# ESP32-Skunk1-OSHPARK.net
KiCad netlist of a schematic drawn in EAGLE
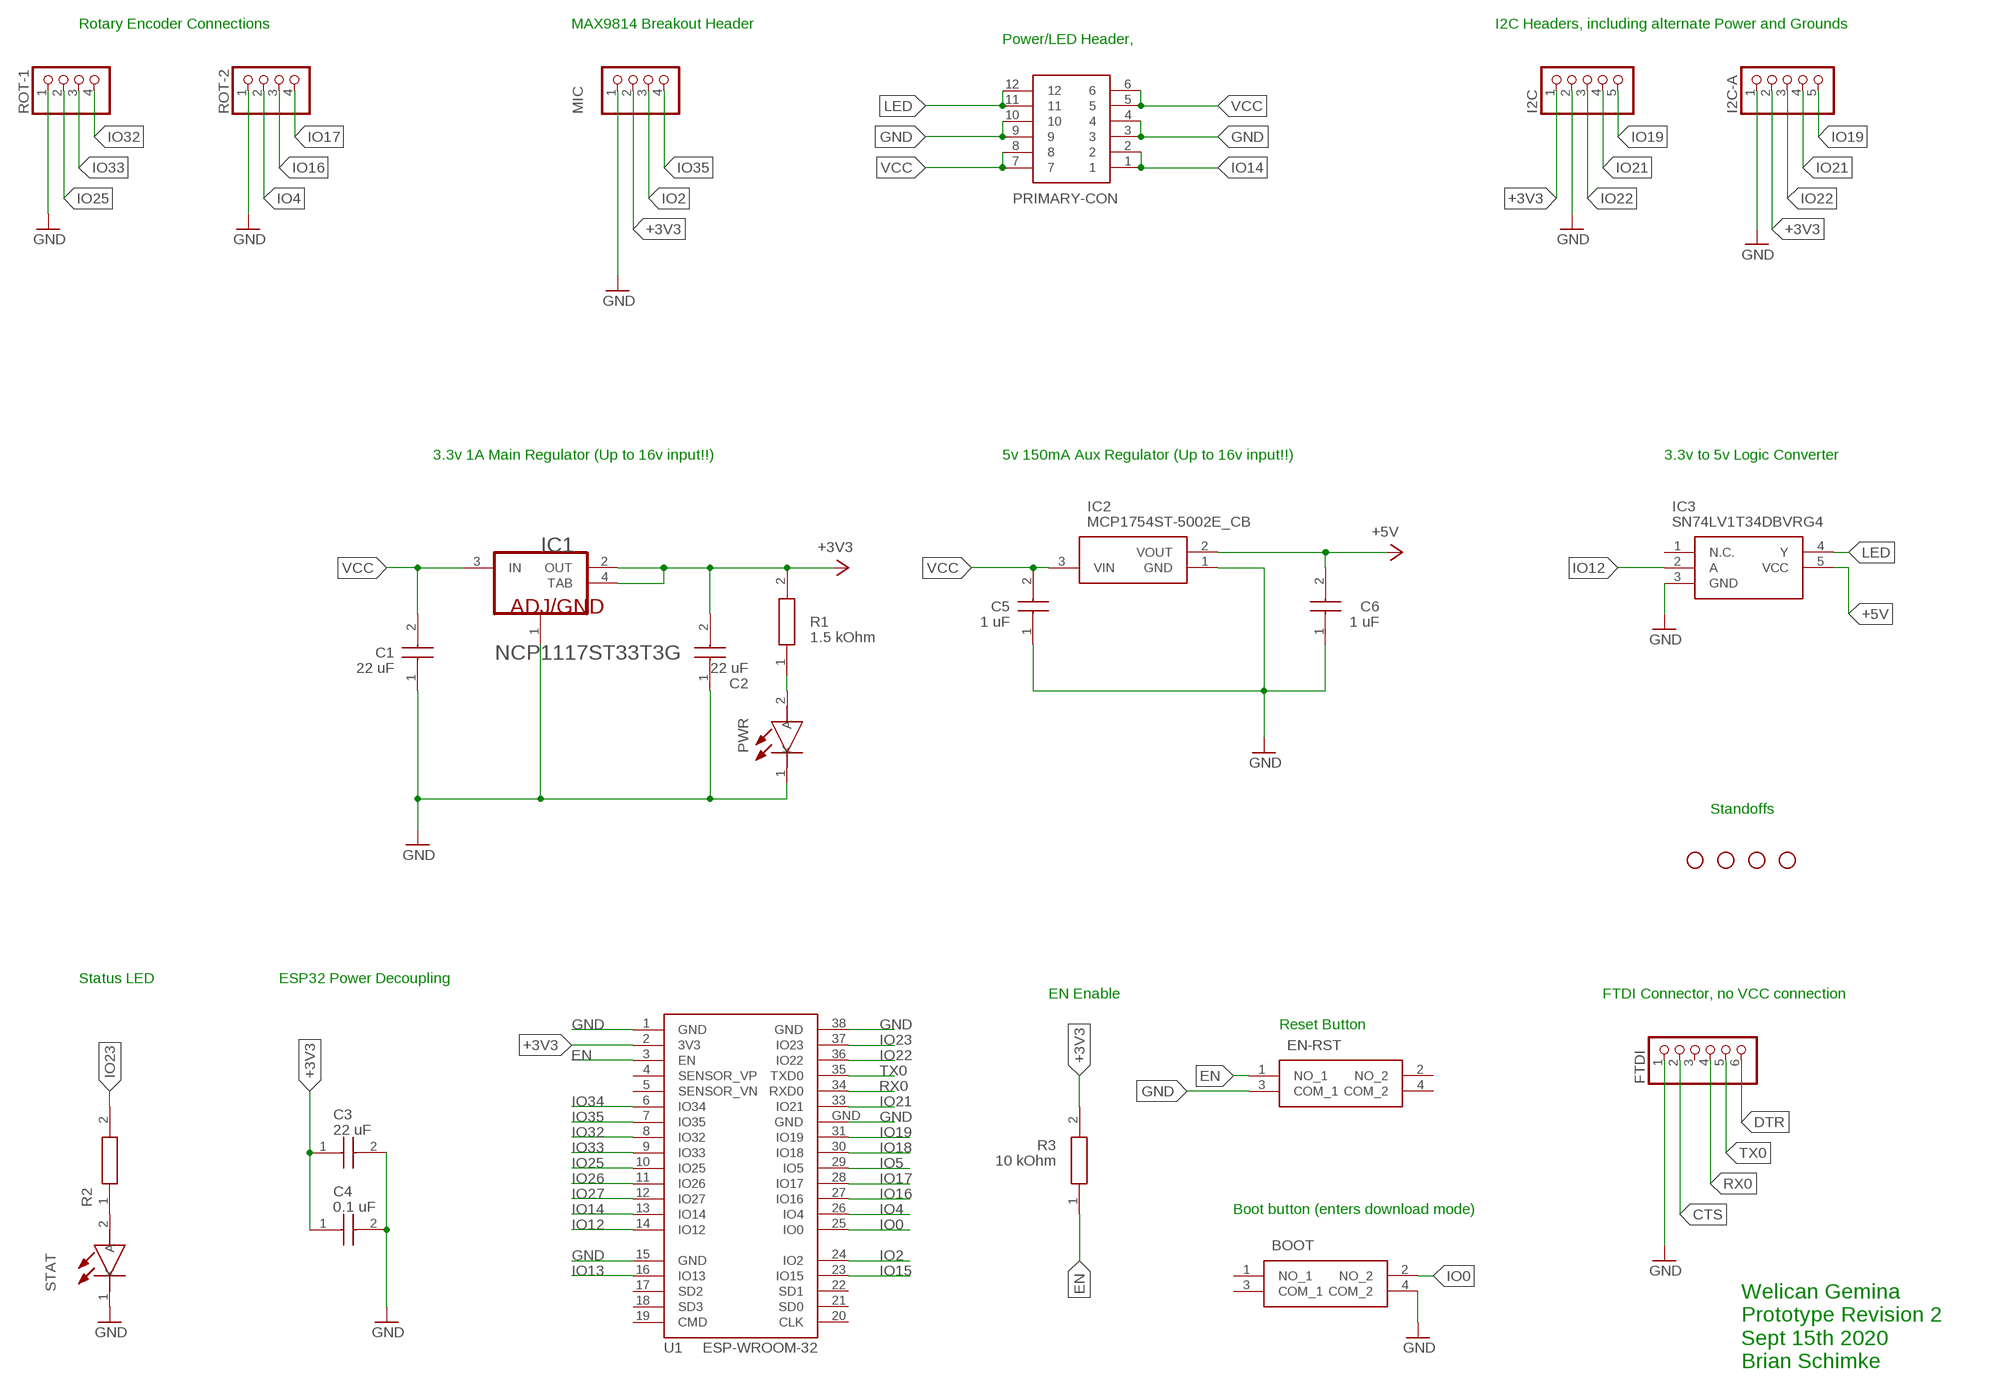
[diagram p0: schematic, sheet 1]

(export (version "E")
  (design (tool "Eeschema 10.0.6"))
  (components
    (comp (ref "BOOT")
      (value "PTS647SK70SMTR2LFS")
      (footprint "eagle-import:PTS647SK70SMTR2LFS")
      (fields (field (name "MOUSER_PART_NUMBER") "611-PTS647SK70SMTR2L"))
      (libsource (lib "eagle-import") (part "PTS647SK70SMTR2LFS"))
    )
    (comp (ref "C1")
      (value "22 uF")
      (footprint "eagle-import:CAPC3216X180N")
      (fields
        (field (name "MANUFACTURER_PART_NUMBER") "C1206C226M4PACTU")
        (field (name "MOUSER_PART_NUMBER") "80-C1206C226M4P")
      )
      (libsource (lib "eagle-import") (part "C1206C226M4PACTU"))
    )
    (comp (ref "C2")
      (value "22 uF")
      (footprint "eagle-import:CAPC3216X180N")
      (fields
        (field (name "MANUFACTURER_PART_NUMBER") "C1206C226M4PACTU")
        (field (name "MOUSER_PART_NUMBER") "80-C1206C226M4P")
      )
      (libsource (lib "eagle-import") (part "C1206C226M4PACTU"))
    )
    (comp (ref "C3")
      (value "22 uF")
      (footprint "eagle-import:CAPC3216X180N")
      (fields
        (field (name "MANUFACTURER_PART_NUMBER") "C1206C226M4PACTU")
        (field (name "MOUSER_PART_NUMBER") "80-C1206C226M4P")
      )
      (libsource (lib "eagle-import") (part "C1206C226M4PACTU"))
    )
    (comp (ref "C4")
      (value "0.1 uF")
      (footprint "eagle-import:CAPC3216X180N")
      (fields
        (field (name "MANUFACTURER_PART_NUMBER") "C1206C226M4PACTU")
        (field (name "MOUSER_PART_NUMBER") "80-C1206C226M4P")
      )
      (libsource (lib "eagle-import") (part "C1206C226M4PACTU"))
    )
    (comp (ref "C5")
      (value "1 uF")
      (footprint "eagle-import:CAPC3216X180N")
      (fields
        (field (name "MANUFACTURER_PART_NUMBER") "C1206C226M4PACTU")
        (field (name "MOUSER_PART_NUMBER") "80-C1206C226M4P")
      )
      (libsource (lib "eagle-import") (part "C1206C226M4PACTU"))
    )
    (comp (ref "C6")
      (value "1 uF")
      (footprint "eagle-import:CAPC3216X180N")
      (fields
        (field (name "MANUFACTURER_PART_NUMBER") "C1206C226M4PACTU")
        (field (name "MOUSER_PART_NUMBER") "80-C1206C226M4P")
      )
      (libsource (lib "eagle-import") (part "C1206C226M4PACTU"))
    )
    (comp (ref "EN-RST")
      (value "PTS647SK70SMTR2LFS")
      (footprint "eagle-import:PTS647SK70SMTR2LFS")
      (fields (field (name "MOUSER_PART_NUMBER") "611-PTS647SK70SMTR2L"))
      (libsource (lib "eagle-import") (part "PTS647SK70SMTR2LFS"))
    )
    (comp (ref "FTDI")
      (value "PINHD-1X6")
      (footprint "eagle-import:1X06")
      (libsource (lib "eagle-import") (part "PINHD-1X6"))
    )
    (comp (ref "H1")
      (value "STAND-OFF")
      (footprint "eagle-import:STAND-OFF")
      (libsource (lib "eagle-import") (part "STAND-OFF"))
    )
    (comp (ref "H2")
      (value "STAND-OFF")
      (footprint "eagle-import:STAND-OFF")
      (libsource (lib "eagle-import") (part "STAND-OFF"))
    )
    (comp (ref "H3")
      (value "STAND-OFF")
      (footprint "eagle-import:STAND-OFF")
      (libsource (lib "eagle-import") (part "STAND-OFF"))
    )
    (comp (ref "H4")
      (value "STAND-OFF")
      (footprint "eagle-import:STAND-OFF")
      (libsource (lib "eagle-import") (part "STAND-OFF"))
    )
    (comp (ref "I2C")
      (value "PINHD-1X5")
      (footprint "eagle-import:1X05")
      (libsource (lib "eagle-import") (part "PINHD-1X5"))
    )
    (comp (ref "I2C-A")
      (value "PINHD-1X5")
      (footprint "eagle-import:1X05")
      (libsource (lib "eagle-import") (part "PINHD-1X5"))
    )
    (comp (ref "IC1")
      (value "ON_SEMICONDUCTOR_NCP1117ST33T3GON_SEMICONDUCTOR_NCP1117ST33T3G_0_0")
      (footprint "eagle-import:ON_SEMICONDUCTOR_NCP1117ST33T3G_0")
      (fields
        (field (name "MF") "ON Semiconductor")
        (field (name "MPN") "NCP1117ST33T3G")
        (field (name "TOLERANCE") "1%")
      )
      (libsource (lib "eagle-import") (part "ON_SEMICONDUCTOR_NCP1117ST33T3GON_SEMICONDUCTOR_NCP1117ST33T3G_0_0"))
    )
    (comp (ref "IC2")
      (value "MCP1754ST-5002E_CB")
      (footprint "eagle-import:SOT95P255X145-3N")
      (fields
        (field (name "MANUFACTURER_PART_NUMBER") "MCP1754ST-5002E/CB")
        (field (name "MOUSER_PART_NUMBER") "579-MCP1754T-5002ECB")
      )
      (libsource (lib "eagle-import") (part "MCP1754ST-5002E_CB"))
    )
    (comp (ref "IC3")
      (value "SN74LV1T34DBVRG4")
      (footprint "eagle-import:SOT95P280X145-5N")
      (fields (field (name "MOUSER_PART_NUMBER") "595-SN74LV1T34DBVRG4"))
      (libsource (lib "eagle-import") (part "SN74LV1T34DBVRG4"))
    )
    (comp (ref "MIC")
      (value "PINHD-1X4")
      (footprint "eagle-import:1X04")
      (libsource (lib "eagle-import") (part "PINHD-1X4"))
    )
    (comp (ref "PRIMARY-CON")
      (value "1-2834015-6")
      (footprint "eagle-import:SHDR12W90P508X254_2X6_1824X128")
      (fields (field (name "MOUSER_PART_NUMBER") "571-1-2834015-6"))
      (libsource (lib "eagle-import") (part "1-2834015-6"))
    )
    (comp (ref "PWR")
      (value "150120AS75000")
      (footprint "eagle-import:LEDSC320X160X78-2N")
      (fields (field (name "MOUSER_PART_NUMBER") "710-150120AS75000"))
      (libsource (lib "eagle-import") (part "150120AS75000"))
    )
    (comp (ref "R1")
      (value "1.5 kOhm")
      (footprint "eagle-import:RESC3216X60N")
      (fields
        (field (name "MANUFACTURER_PART_NUMBER") "CRCW12061K00FKEB")
        (field (name "MOUSER_PART_NUMBER") "71-CRCW12061K00FKEB")
      )
      (libsource (lib "eagle-import") (part "CRCW12061K00FKEB"))
    )
    (comp (ref "R2")
      (value "CRCW12061K00FKEB")
      (footprint "eagle-import:RESC3216X60N")
      (fields (field (name "MOUSER_PART_NUMBER") "71-CRCW12061K00FKEB"))
      (libsource (lib "eagle-import") (part "CRCW12061K00FKEB"))
    )
    (comp (ref "R3")
      (value "10 kOhm")
      (footprint "eagle-import:RESC3216X60N")
      (fields
        (field (name "MANUFACTURER_PART_NUMBER") "CRCW12061K00FKEB")
        (field (name "MOUSER_PART_NUMBER") "71-CRCW12061K00FKEB")
      )
      (libsource (lib "eagle-import") (part "CRCW12061K00FKEB"))
    )
    (comp (ref "ROT-1")
      (value "PINHD-1X4")
      (footprint "eagle-import:1X04")
      (libsource (lib "eagle-import") (part "PINHD-1X4"))
    )
    (comp (ref "ROT-2")
      (value "PINHD-1X4")
      (footprint "eagle-import:1X04")
      (libsource (lib "eagle-import") (part "PINHD-1X4"))
    )
    (comp (ref "STAT")
      (value "150120AS75000")
      (footprint "eagle-import:LEDSC320X160X78-2N")
      (fields (field (name "MOUSER_PART_NUMBER") "710-150120AS75000"))
      (libsource (lib "eagle-import") (part "150120AS75000"))
    )
    (comp (ref "U1")
      (value "ESP-WROOM-32")
      (footprint "eagle-import:ESP-WROOM-32")
      (libsource (lib "eagle-import") (part "ESP-WROOM-32"))
    )
  )
  (nets
    (net (code "1") (name "+3V3") (class "Default")
      (node (ref "C2") (pin "2") (pinfunction "2_2") (pintype "bidirectional"))
      (node (ref "C3") (pin "1") (pinfunction "1_1") (pintype "bidirectional"))
      (node (ref "C4") (pin "1") (pinfunction "1_1") (pintype "bidirectional"))
      (node (ref "I2C") (pin "1") (pinfunction "1_1") (pintype "passive"))
      (node (ref "I2C-A") (pin "2") (pinfunction "2_2") (pintype "passive"))
      (node (ref "IC1") (pin "2") (pinfunction "OUT_2") (pintype "power_in"))
      (node (ref "IC1") (pin "4") (pinfunction "TAB_4") (pintype "passive"))
      (node (ref "MIC") (pin "2") (pinfunction "2_2") (pintype "passive"))
      (node (ref "R1") (pin "2") (pinfunction "2_2") (pintype "bidirectional"))
      (node (ref "R3") (pin "2") (pinfunction "2_2") (pintype "bidirectional"))
      (node (ref "U1") (pin "2") (pinfunction "3V3_2") (pintype "power_in"))
    )
    (net (code "2") (name "+5V") (class "Default")
      (node (ref "C6") (pin "2") (pinfunction "2_2") (pintype "bidirectional"))
      (node (ref "IC2") (pin "2") (pinfunction "VOUT_2") (pintype "bidirectional"))
      (node (ref "IC3") (pin "5") (pinfunction "VCC_5") (pintype "bidirectional"))
    )
    (net (code "3") (name "/IO5") (class "Default")
      (node (ref "U1") (pin "29") (pinfunction "IO5_29") (pintype "bidirectional"))
    )
    (net (code "4") (name "/IO13") (class "Default")
      (node (ref "U1") (pin "16") (pinfunction "IO13_16") (pintype "bidirectional"))
    )
    (net (code "5") (name "/IO15") (class "Default")
      (node (ref "U1") (pin "23") (pinfunction "IO15_23") (pintype "bidirectional"))
    )
    (net (code "6") (name "/IO18") (class "Default")
      (node (ref "U1") (pin "30") (pinfunction "IO18_30") (pintype "bidirectional"))
    )
    (net (code "7") (name "/IO26") (class "Default")
      (node (ref "U1") (pin "11") (pinfunction "IO26_11") (pintype "bidirectional"))
    )
    (net (code "8") (name "/IO27") (class "Default")
      (node (ref "U1") (pin "12") (pinfunction "IO27_12") (pintype "bidirectional"))
    )
    (net (code "9") (name "/IO34") (class "Default")
      (node (ref "U1") (pin "6") (pinfunction "IO34_6") (pintype "bidirectional"))
    )
    (net (code "10") (name "CTS") (class "Default")
      (node (ref "FTDI") (pin "2") (pinfunction "2_2") (pintype "passive"))
    )
    (net (code "11") (name "DTR") (class "Default")
      (node (ref "FTDI") (pin "6") (pinfunction "6_6") (pintype "passive"))
    )
    (net (code "12") (name "EN") (class "Default")
      (node (ref "EN-RST") (pin "1") (pinfunction "NO_1_1") (pintype "bidirectional"))
      (node (ref "R3") (pin "1") (pinfunction "1_1") (pintype "bidirectional"))
      (node (ref "U1") (pin "3") (pinfunction "EN_3") (pintype "input"))
    )
    (net (code "13") (name "GND") (class "Default")
      (node (ref "BOOT") (pin "4") (pinfunction "COM_2_4") (pintype "bidirectional"))
      (node (ref "C1") (pin "1") (pinfunction "1_1") (pintype "bidirectional"))
      (node (ref "C2") (pin "1") (pinfunction "1_1") (pintype "bidirectional"))
      (node (ref "C3") (pin "2") (pinfunction "2_2") (pintype "bidirectional"))
      (node (ref "C4") (pin "2") (pinfunction "2_2") (pintype "bidirectional"))
      (node (ref "C5") (pin "1") (pinfunction "1_1") (pintype "bidirectional"))
      (node (ref "C6") (pin "1") (pinfunction "1_1") (pintype "bidirectional"))
      (node (ref "EN-RST") (pin "3") (pinfunction "COM_1_3") (pintype "bidirectional"))
      (node (ref "FTDI") (pin "1") (pinfunction "1_1") (pintype "passive"))
      (node (ref "I2C") (pin "2") (pinfunction "2_2") (pintype "passive"))
      (node (ref "I2C-A") (pin "1") (pinfunction "1_1") (pintype "passive"))
      (node (ref "IC1") (pin "1") (pinfunction "ADJ/GND_1") (pintype "passive"))
      (node (ref "IC2") (pin "1") (pinfunction "GND_1") (pintype "bidirectional"))
      (node (ref "IC3") (pin "3") (pinfunction "GND_3") (pintype "bidirectional"))
      (node (ref "MIC") (pin "1") (pinfunction "1_1") (pintype "passive"))
      (node (ref "PRIMARY-CON") (pin "10") (pinfunction "10_10") (pintype "bidirectional"))
      (node (ref "PRIMARY-CON") (pin "3") (pinfunction "3_3") (pintype "bidirectional"))
      (node (ref "PRIMARY-CON") (pin "4") (pinfunction "4_4") (pintype "bidirectional"))
      (node (ref "PRIMARY-CON") (pin "9") (pinfunction "9_9") (pintype "bidirectional"))
      (node (ref "PWR") (pin "1") (pinfunction "K_1") (pintype "bidirectional"))
      (node (ref "ROT-1") (pin "1") (pinfunction "1_1") (pintype "passive"))
      (node (ref "ROT-2") (pin "1") (pinfunction "1_1") (pintype "passive"))
      (node (ref "STAT") (pin "1") (pinfunction "K_1") (pintype "bidirectional"))
      (node (ref "U1") (pin "1") (pinfunction "GND_1") (pintype "power_in"))
      (node (ref "U1") (pin "15") (pinfunction "GND_15") (pintype "power_in"))
      (node (ref "U1") (pin "38") (pinfunction "GND_38") (pintype "power_in"))
      (node (ref "U1") (pin "GND") (pinfunction "GND_GND") (pintype "power_in"))
    )
    (net (code "14") (name "IO0") (class "Default")
      (node (ref "BOOT") (pin "2") (pinfunction "NO_2_2") (pintype "bidirectional"))
      (node (ref "U1") (pin "25") (pinfunction "IO0_25") (pintype "bidirectional"))
    )
    (net (code "15") (name "IO2") (class "Default")
      (node (ref "MIC") (pin "3") (pinfunction "3_3") (pintype "passive"))
      (node (ref "U1") (pin "24") (pinfunction "IO2_24") (pintype "bidirectional"))
    )
    (net (code "16") (name "IO4") (class "Default")
      (node (ref "ROT-2") (pin "2") (pinfunction "2_2") (pintype "passive"))
      (node (ref "U1") (pin "26") (pinfunction "IO4_26") (pintype "bidirectional"))
    )
    (net (code "17") (name "IO12") (class "Default")
      (node (ref "IC3") (pin "2") (pinfunction "A_2") (pintype "bidirectional"))
      (node (ref "U1") (pin "14") (pinfunction "IO12_14") (pintype "bidirectional"))
    )
    (net (code "18") (name "IO14") (class "Default")
      (node (ref "PRIMARY-CON") (pin "1") (pinfunction "1_1") (pintype "bidirectional"))
      (node (ref "PRIMARY-CON") (pin "2") (pinfunction "2_2") (pintype "bidirectional"))
      (node (ref "U1") (pin "13") (pinfunction "IO14_13") (pintype "bidirectional"))
    )
    (net (code "19") (name "IO16") (class "Default")
      (node (ref "ROT-2") (pin "3") (pinfunction "3_3") (pintype "passive"))
      (node (ref "U1") (pin "27") (pinfunction "IO16_27") (pintype "bidirectional"))
    )
    (net (code "20") (name "IO17") (class "Default")
      (node (ref "ROT-2") (pin "4") (pinfunction "4_4") (pintype "passive"))
      (node (ref "U1") (pin "28") (pinfunction "IO17_28") (pintype "bidirectional"))
    )
    (net (code "21") (name "IO19") (class "Default")
      (node (ref "I2C") (pin "5") (pinfunction "5_5") (pintype "passive"))
      (node (ref "I2C-A") (pin "5") (pinfunction "5_5") (pintype "passive"))
      (node (ref "U1") (pin "31") (pinfunction "IO19_31") (pintype "bidirectional"))
    )
    (net (code "22") (name "IO21") (class "Default")
      (node (ref "I2C") (pin "4") (pinfunction "4_4") (pintype "passive"))
      (node (ref "I2C-A") (pin "4") (pinfunction "4_4") (pintype "passive"))
      (node (ref "U1") (pin "33") (pinfunction "IO21_33") (pintype "bidirectional"))
    )
    (net (code "23") (name "IO22") (class "Default")
      (node (ref "I2C") (pin "3") (pinfunction "3_3") (pintype "passive"))
      (node (ref "I2C-A") (pin "3") (pinfunction "3_3") (pintype "passive"))
      (node (ref "U1") (pin "36") (pinfunction "IO22_36") (pintype "bidirectional"))
    )
    (net (code "24") (name "IO23") (class "Default")
      (node (ref "R2") (pin "2") (pinfunction "2_2") (pintype "bidirectional"))
      (node (ref "U1") (pin "37") (pinfunction "IO23_37") (pintype "bidirectional"))
    )
    (net (code "25") (name "IO25") (class "Default")
      (node (ref "ROT-1") (pin "2") (pinfunction "2_2") (pintype "passive"))
      (node (ref "U1") (pin "10") (pinfunction "IO25_10") (pintype "bidirectional"))
    )
    (net (code "26") (name "IO32") (class "Default")
      (node (ref "ROT-1") (pin "4") (pinfunction "4_4") (pintype "passive"))
      (node (ref "U1") (pin "8") (pinfunction "IO32_8") (pintype "bidirectional"))
    )
    (net (code "27") (name "IO33") (class "Default")
      (node (ref "ROT-1") (pin "3") (pinfunction "3_3") (pintype "passive"))
      (node (ref "U1") (pin "9") (pinfunction "IO33_9") (pintype "bidirectional"))
    )
    (net (code "28") (name "IO35") (class "Default")
      (node (ref "MIC") (pin "4") (pinfunction "4_4") (pintype "passive"))
      (node (ref "U1") (pin "7") (pinfunction "IO35_7") (pintype "bidirectional"))
    )
    (net (code "29") (name "LED") (class "Default")
      (node (ref "IC3") (pin "4") (pinfunction "Y_4") (pintype "bidirectional"))
      (node (ref "PRIMARY-CON") (pin "11") (pinfunction "11_11") (pintype "bidirectional"))
      (node (ref "PRIMARY-CON") (pin "12") (pinfunction "12_12") (pintype "bidirectional"))
    )
    (net (code "30") (name "Net-(PWR-A)") (class "Default")
      (node (ref "PWR") (pin "2") (pinfunction "A_2") (pintype "bidirectional"))
      (node (ref "R1") (pin "1") (pinfunction "1_1") (pintype "bidirectional"))
    )
    (net (code "31") (name "Net-(STAT-A)") (class "Default")
      (node (ref "R2") (pin "1") (pinfunction "1_1") (pintype "bidirectional"))
      (node (ref "STAT") (pin "2") (pinfunction "A_2") (pintype "bidirectional"))
    )
    (net (code "32") (name "RX0") (class "Default")
      (node (ref "FTDI") (pin "4") (pinfunction "4_4") (pintype "passive"))
      (node (ref "U1") (pin "34") (pinfunction "RXD0_34") (pintype "bidirectional"))
    )
    (net (code "33") (name "TX0") (class "Default")
      (node (ref "FTDI") (pin "5") (pinfunction "5_5") (pintype "passive"))
      (node (ref "U1") (pin "35") (pinfunction "TXD0_35") (pintype "bidirectional"))
    )
    (net (code "34") (name "VCC") (class "Default")
      (node (ref "C1") (pin "2") (pinfunction "2_2") (pintype "bidirectional"))
      (node (ref "C5") (pin "2") (pinfunction "2_2") (pintype "bidirectional"))
      (node (ref "IC1") (pin "3") (pinfunction "IN_3") (pintype "power_in"))
      (node (ref "IC2") (pin "3") (pinfunction "VIN_3") (pintype "bidirectional"))
      (node (ref "PRIMARY-CON") (pin "5") (pinfunction "5_5") (pintype "bidirectional"))
      (node (ref "PRIMARY-CON") (pin "6") (pinfunction "6_6") (pintype "bidirectional"))
      (node (ref "PRIMARY-CON") (pin "7") (pinfunction "7_7") (pintype "bidirectional"))
      (node (ref "PRIMARY-CON") (pin "8") (pinfunction "8_8") (pintype "bidirectional"))
    )
    (net (code "35") (name "unconnected-(BOOT-COM_1-Pad3)") (class "Default")
      (node (ref "BOOT") (pin "3") (pinfunction "COM_1_3") (pintype "bidirectional"))
    )
    (net (code "36") (name "unconnected-(BOOT-NO_1-Pad1)") (class "Default")
      (node (ref "BOOT") (pin "1") (pinfunction "NO_1_1") (pintype "bidirectional"))
    )
    (net (code "37") (name "unconnected-(EN-RST-COM_2-Pad4)") (class "Default")
      (node (ref "EN-RST") (pin "4") (pinfunction "COM_2_4") (pintype "bidirectional"))
    )
    (net (code "38") (name "unconnected-(EN-RST-NO_2-Pad2)") (class "Default")
      (node (ref "EN-RST") (pin "2") (pinfunction "NO_2_2") (pintype "bidirectional"))
    )
    (net (code "39") (name "unconnected-(FTDI-Pad3)") (class "Default")
      (node (ref "FTDI") (pin "3") (pinfunction "3_3") (pintype "passive"))
    )
    (net (code "40") (name "unconnected-(IC3-N.C.-Pad1)") (class "Default")
      (node (ref "IC3") (pin "1") (pinfunction "N.C._1") (pintype "no_connect"))
    )
    (net (code "41") (name "unconnected-(U1-CLK-Pad20)") (class "Default")
      (node (ref "U1") (pin "20") (pinfunction "CLK_20") (pintype "bidirectional"))
    )
    (net (code "42") (name "unconnected-(U1-CMD-Pad19)") (class "Default")
      (node (ref "U1") (pin "19") (pinfunction "CMD_19") (pintype "bidirectional"))
    )
    (net (code "43") (name "unconnected-(U1-SD0-Pad21)") (class "Default")
      (node (ref "U1") (pin "21") (pinfunction "SD0_21") (pintype "bidirectional"))
    )
    (net (code "44") (name "unconnected-(U1-SD1-Pad22)") (class "Default")
      (node (ref "U1") (pin "22") (pinfunction "SD1_22") (pintype "bidirectional"))
    )
    (net (code "45") (name "unconnected-(U1-SD2-Pad17)") (class "Default")
      (node (ref "U1") (pin "17") (pinfunction "SD2_17") (pintype "bidirectional"))
    )
    (net (code "46") (name "unconnected-(U1-SD3-Pad18)") (class "Default")
      (node (ref "U1") (pin "18") (pinfunction "SD3_18") (pintype "bidirectional"))
    )
    (net (code "47") (name "unconnected-(U1-SENSOR_VN-Pad5)") (class "Default")
      (node (ref "U1") (pin "5") (pinfunction "SENSOR_VN_5") (pintype "bidirectional"))
    )
    (net (code "48") (name "unconnected-(U1-SENSOR_VP-Pad4)") (class "Default")
      (node (ref "U1") (pin "4") (pinfunction "SENSOR_VP_4") (pintype "bidirectional"))
    )
  )
)
